# Fader_Control_Attiny85.net
KiCad netlist of a schematic drawn in EAGLE
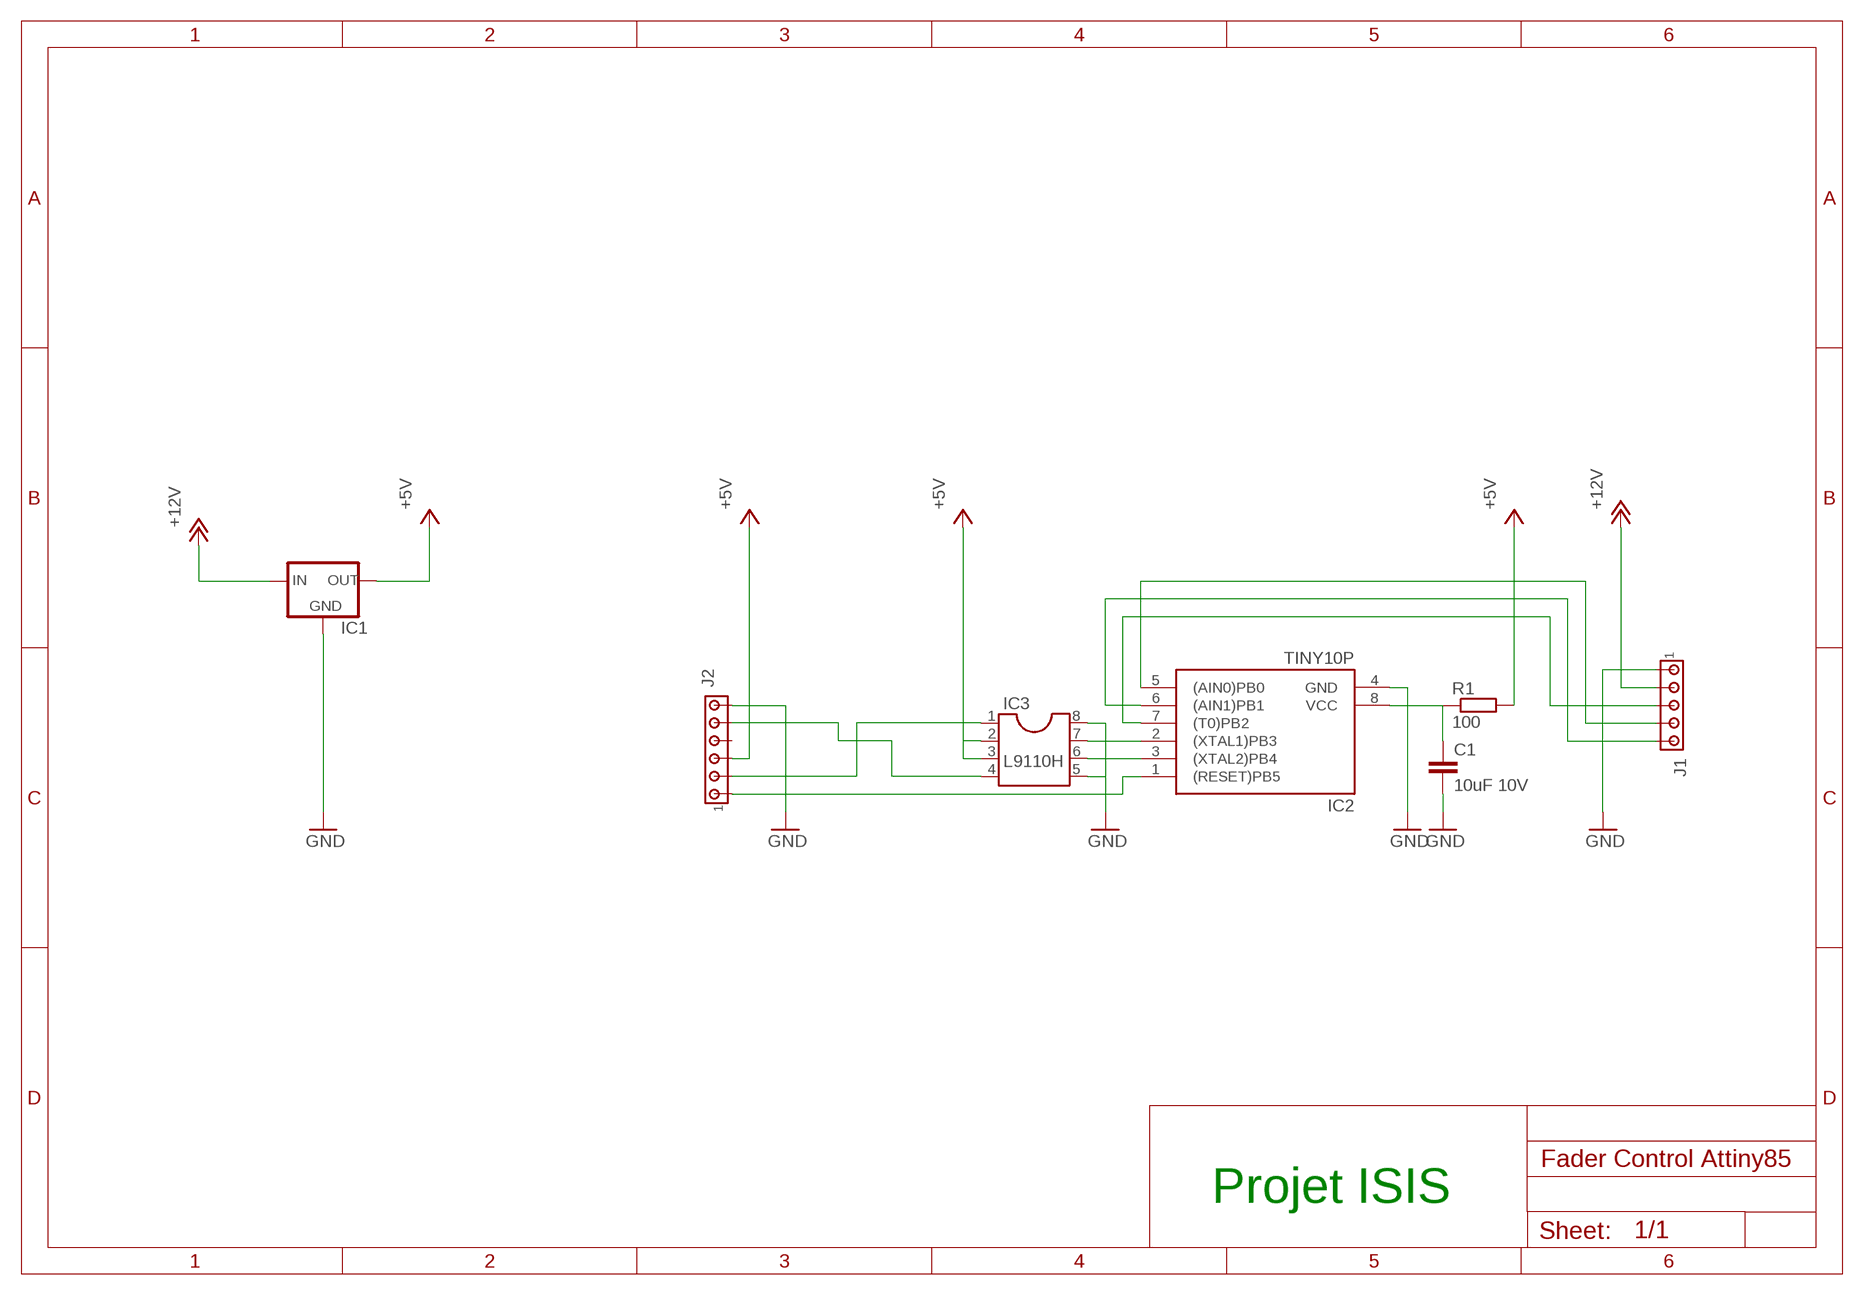
[diagram p0: schematic, sheet 1]

(export (version "E")
  (design (tool "Eeschema 10.0.6"))
  (components
    (comp (ref "C1")
      (value "10uF 10V")
      (footprint "eagle-import:C050-024X044")
      (libsource (lib "eagle-import") (part "C-EU050-024X044"))
    )
    (comp (ref "IC1")
      (value "78MXXS")
      (footprint "eagle-import:78MXXS")
      (libsource (lib "eagle-import") (part "78MXXS"))
    )
    (comp (ref "IC2")
      (value "TINY10P")
      (footprint "eagle-import:DIL08")
      (libsource (lib "eagle-import") (part "TINY10P"))
    )
    (comp (ref "IC3")
      (value "L9110H")
      (footprint "eagle-import:DIL08")
      (libsource (lib "eagle-import") (part "DIL8"))
    )
    (comp (ref "J1")
      (value "MTA05-100")
      (footprint "eagle-import:10X05MTA")
      (libsource (lib "eagle-import") (part "MTA05-100"))
    )
    (comp (ref "J2")
      (value "MTA06-100")
      (footprint "eagle-import:10X06MTA")
      (libsource (lib "eagle-import") (part "MTA06-100"))
    )
    (comp (ref "R1")
      (value "100")
      (footprint "eagle-import:0204_7")
      (libsource (lib "eagle-import") (part "R-EU_0204/7"))
    )
  )
  (nets
    (net (code "1") (name "+5V") (class "Default")
      (node (ref "IC1") (pin "OUT") (pinfunction "OUT_OUT") (pintype "passive"))
      (node (ref "IC3") (pin "2") (pinfunction "2_2") (pintype "passive"))
      (node (ref "IC3") (pin "3") (pinfunction "3_3") (pintype "passive"))
      (node (ref "J2") (pin "3") (pinfunction "3_3") (pintype "passive"))
      (node (ref "R1") (pin "2") (pinfunction "2_2") (pintype "passive"))
    )
    (net (code "2") (name "+12V") (class "Default")
      (node (ref "IC1") (pin "IN") (pinfunction "IN_IN") (pintype "input"))
      (node (ref "J1") (pin "2") (pinfunction "2_2") (pintype "passive"))
    )
    (net (code "3") (name "GND") (class "Default")
      (node (ref "C1") (pin "2") (pinfunction "2_2") (pintype "passive"))
      (node (ref "IC1") (pin "GND") (pinfunction "GND_GND") (pintype "input"))
      (node (ref "IC2") (pin "4") (pinfunction "GND_4") (pintype "power_in"))
      (node (ref "IC3") (pin "5") (pinfunction "5_5") (pintype "passive"))
      (node (ref "IC3") (pin "8") (pinfunction "8_8") (pintype "passive"))
      (node (ref "J1") (pin "1") (pinfunction "1_1") (pintype "passive"))
      (node (ref "J2") (pin "6") (pinfunction "6_6") (pintype "passive"))
    )
    (net (code "4") (name "Net-(IC2-(AIN0)PB0)") (class "Default")
      (node (ref "IC2") (pin "5") (pinfunction "(AIN0)PB0_5") (pintype "bidirectional"))
      (node (ref "J1") (pin "4") (pinfunction "4_4") (pintype "passive"))
    )
    (net (code "5") (name "Net-(IC2-(AIN1)PB1)") (class "Default")
      (node (ref "IC2") (pin "6") (pinfunction "(AIN1)PB1_6") (pintype "bidirectional"))
      (node (ref "J1") (pin "5") (pinfunction "5_5") (pintype "passive"))
    )
    (net (code "6") (name "Net-(IC2-(RESET)PB5)") (class "Default")
      (node (ref "IC2") (pin "1") (pinfunction "(RESET)PB5_1") (pintype "bidirectional"))
      (node (ref "J2") (pin "1") (pinfunction "1_1") (pintype "passive"))
    )
    (net (code "7") (name "Net-(IC2-(T0)PB2)") (class "Default")
      (node (ref "IC2") (pin "7") (pinfunction "(T0)PB2_7") (pintype "bidirectional"))
      (node (ref "J1") (pin "3") (pinfunction "3_3") (pintype "passive"))
    )
    (net (code "8") (name "Net-(IC2-(XTAL1)PB3)") (class "Default")
      (node (ref "IC2") (pin "2") (pinfunction "(XTAL1)PB3_2") (pintype "bidirectional"))
      (node (ref "IC3") (pin "7") (pinfunction "7_7") (pintype "passive"))
    )
    (net (code "9") (name "Net-(IC2-(XTAL2)PB4)") (class "Default")
      (node (ref "IC2") (pin "3") (pinfunction "(XTAL2)PB4_3") (pintype "bidirectional"))
      (node (ref "IC3") (pin "6") (pinfunction "6_6") (pintype "passive"))
    )
    (net (code "10") (name "Net-(IC2-VCC)") (class "Default")
      (node (ref "C1") (pin "1") (pinfunction "1_1") (pintype "passive"))
      (node (ref "IC2") (pin "8") (pinfunction "VCC_8") (pintype "power_in"))
      (node (ref "R1") (pin "1") (pinfunction "1_1") (pintype "passive"))
    )
    (net (code "11") (name "Net-(IC3-Pad1)") (class "Default")
      (node (ref "IC3") (pin "1") (pinfunction "1_1") (pintype "passive"))
      (node (ref "J2") (pin "2") (pinfunction "2_2") (pintype "passive"))
    )
    (net (code "12") (name "Net-(IC3-Pad4)") (class "Default")
      (node (ref "IC3") (pin "4") (pinfunction "4_4") (pintype "passive"))
      (node (ref "J2") (pin "5") (pinfunction "5_5") (pintype "passive"))
    )
    (net (code "13") (name "unconnected-(J2-Pad4)") (class "Default")
      (node (ref "J2") (pin "4") (pinfunction "4_4") (pintype "passive"))
    )
  )
)
